# flight_teeny.net
KiCad netlist of a schematic drawn in EAGLE
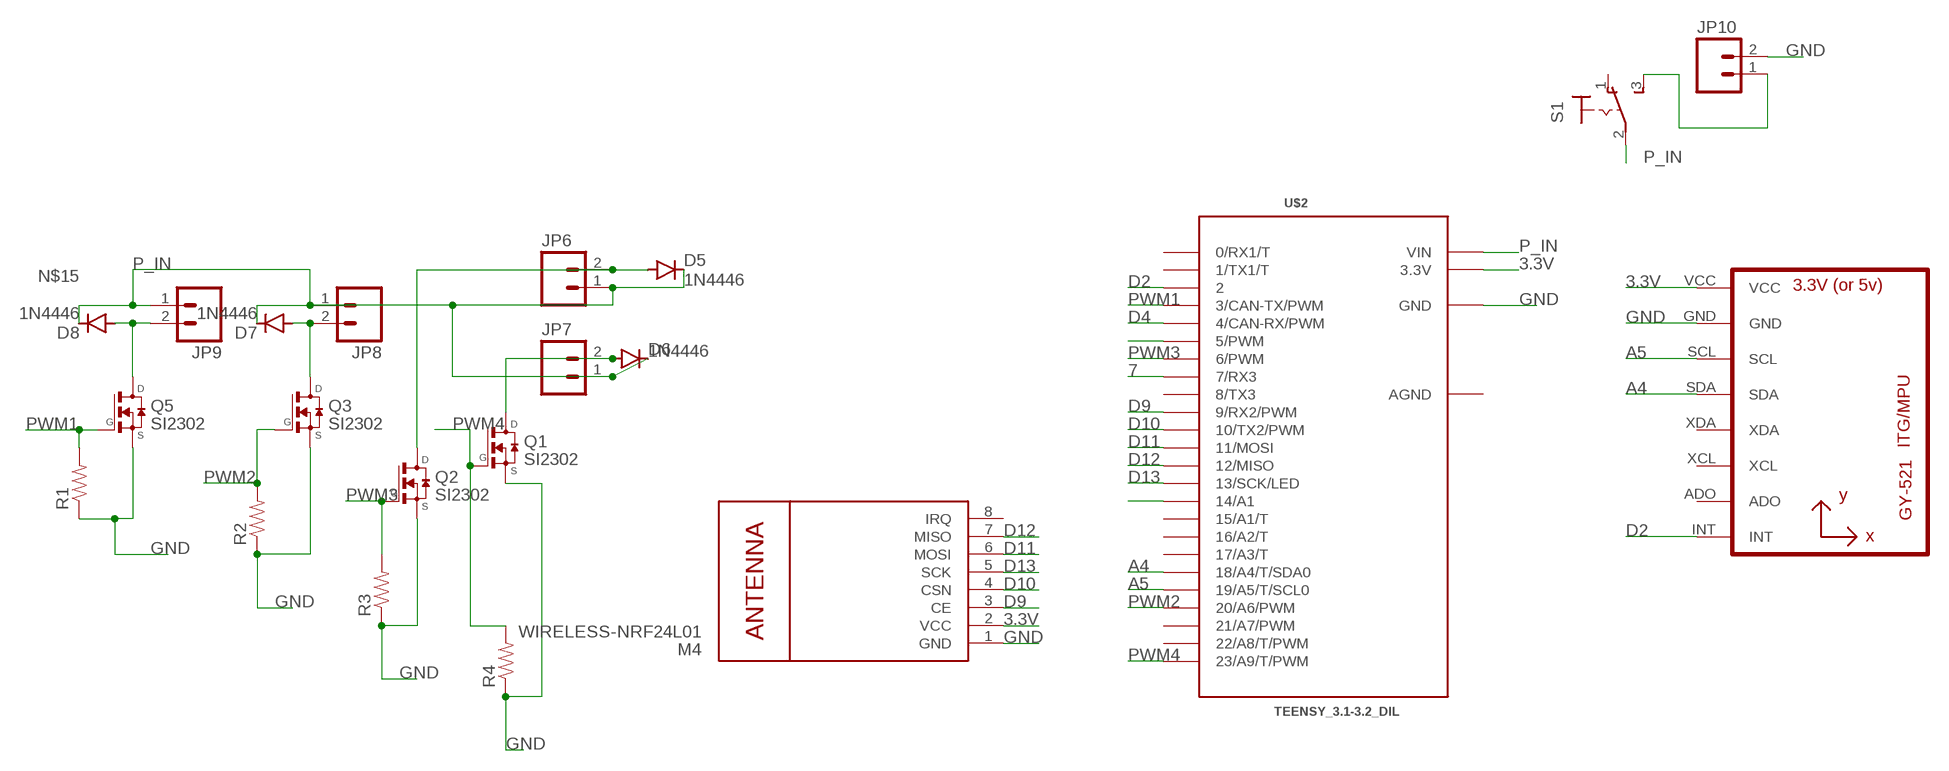
[diagram p0: schematic, sheet 1]

(export (version "E")
  (design (tool "Eeschema 10.0.6"))
  (components
    (comp (ref "D5")
      (value "1N4446")
      (footprint "eagle-import:DO35-10")
      (libsource (lib "eagle-import") (part "1N4446"))
    )
    (comp (ref "D6")
      (value "1N4446")
      (footprint "eagle-import:DO35-10")
      (libsource (lib "eagle-import") (part "1N4446"))
    )
    (comp (ref "D7")
      (value "1N4446")
      (footprint "eagle-import:DO35-10")
      (libsource (lib "eagle-import") (part "1N4446"))
    )
    (comp (ref "D8")
      (value "1N4446")
      (footprint "eagle-import:DO35-10")
      (libsource (lib "eagle-import") (part "1N4446"))
    )
    (comp (ref "JP6")
      (value "M021X02_NO_SILK")
      (footprint "eagle-import:1X02_NO_SILK")
      (libsource (lib "eagle-import") (part "M021X02_NO_SILK"))
    )
    (comp (ref "JP7")
      (value "M021X02_NO_SILK")
      (footprint "eagle-import:1X02_NO_SILK")
      (libsource (lib "eagle-import") (part "M021X02_NO_SILK"))
    )
    (comp (ref "JP8")
      (value "M021X02_NO_SILK")
      (footprint "eagle-import:1X02_NO_SILK")
      (libsource (lib "eagle-import") (part "M021X02_NO_SILK"))
    )
    (comp (ref "JP9")
      (value "M021X02_NO_SILK")
      (footprint "eagle-import:1X02_NO_SILK")
      (libsource (lib "eagle-import") (part "M021X02_NO_SILK"))
    )
    (comp (ref "JP10")
      (value "M02PTH")
      (footprint "eagle-import:1X02")
      (libsource (lib "eagle-import") (part "M02PTH"))
    )
    (comp (ref "M4")
      (value "WIRELESS-NRF24L01")
      (footprint "eagle-import:WIRELESS-NRF24L01")
      (libsource (lib "eagle-import") (part "WIRELESS-NRF24L01"))
    )
    (comp (ref "Q1")
      (value "SI2302")
      (footprint "eagle-import:SOT23")
      (libsource (lib "eagle-import") (part "SI2302"))
    )
    (comp (ref "Q2")
      (value "SI2302")
      (footprint "eagle-import:SOT23")
      (libsource (lib "eagle-import") (part "SI2302"))
    )
    (comp (ref "Q3")
      (value "SI2302")
      (footprint "eagle-import:SOT23")
      (libsource (lib "eagle-import") (part "SI2302"))
    )
    (comp (ref "Q5")
      (value "SI2302")
      (footprint "eagle-import:SOT23")
      (libsource (lib "eagle-import") (part "SI2302"))
    )
    (comp (ref "R1")
      (value "RESISTORAXIAL-0.3")
      (footprint "eagle-import:AXIAL-0.3")
      (libsource (lib "eagle-import") (part "RESISTORAXIAL-0.3"))
    )
    (comp (ref "R2")
      (value "RESISTORAXIAL-0.3")
      (footprint "eagle-import:AXIAL-0.3")
      (libsource (lib "eagle-import") (part "RESISTORAXIAL-0.3"))
    )
    (comp (ref "R3")
      (value "RESISTORAXIAL-0.3")
      (footprint "eagle-import:AXIAL-0.3")
      (libsource (lib "eagle-import") (part "RESISTORAXIAL-0.3"))
    )
    (comp (ref "R4")
      (value "RESISTORAXIAL-0.3")
      (footprint "eagle-import:AXIAL-0.3")
      (libsource (lib "eagle-import") (part "RESISTORAXIAL-0.3"))
    )
    (comp (ref "S1")
      (value "M9040P")
      (footprint "eagle-import:M9040P")
      (libsource (lib "eagle-import") (part "M9040P"))
    )
    (comp (ref "U$2")
      (value "TEENSY_3.1-3.2_DIL")
      (footprint "eagle-import:TEENSY_3.0-3.2&LC_DIL")
      (libsource (lib "eagle-import") (part "TEENSY_3.1-3.2_DIL"))
    )
    (comp (ref "U2")
      (value "GY-521MPU6050")
      (footprint "eagle-import:GY-521")
      (libsource (lib "eagle-import") (part "GY-521MPU6050"))
    )
  )
  (nets
    (net (code "1") (name "/3.3V") (class "Default")
      (node (ref "M4") (pin "2") (pinfunction "VCC_2") (pintype "power_in"))
      (node (ref "U$2") (pin "3.3V") (pinfunction "3.3V_3.3V") (pintype "power_in"))
      (node (ref "U2") (pin "VCC") (pinfunction "VCC_VCC") (pintype "bidirectional"))
    )
    (net (code "2") (name "/7") (class "Default")
      (node (ref "U$2") (pin "7") (pinfunction "7/RX3_7") (pintype "bidirectional"))
    )
    (net (code "3") (name "/A4") (class "Default")
      (node (ref "U$2") (pin "18/A4") (pinfunction "18/A4/T/SDA0_18/A4") (pintype "bidirectional"))
      (node (ref "U2") (pin "SDA") (pinfunction "SDA_SDA") (pintype "bidirectional"))
    )
    (net (code "4") (name "/A5") (class "Default")
      (node (ref "U$2") (pin "19/A5") (pinfunction "19/A5/T/SCL0_19/A5") (pintype "bidirectional"))
      (node (ref "U2") (pin "SCL") (pinfunction "SCL_SCL") (pintype "bidirectional"))
    )
    (net (code "5") (name "/AGND") (class "Default")
      (node (ref "U$2") (pin "AGND") (pinfunction "AGND_AGND") (pintype "power_in"))
    )
    (net (code "6") (name "/D2") (class "Default")
      (node (ref "U$2") (pin "2") (pinfunction "2_2") (pintype "bidirectional"))
      (node (ref "U2") (pin "INT") (pinfunction "INT_INT") (pintype "bidirectional"))
    )
    (net (code "7") (name "/D4") (class "Default")
      (node (ref "U$2") (pin "4") (pinfunction "4/CAN-RX/PWM_4") (pintype "bidirectional"))
    )
    (net (code "8") (name "/D9") (class "Default")
      (node (ref "M4") (pin "3") (pinfunction "CE_3") (pintype "bidirectional"))
      (node (ref "U$2") (pin "9") (pinfunction "9/RX2/PWM_9") (pintype "bidirectional"))
    )
    (net (code "9") (name "/D10") (class "Default")
      (node (ref "M4") (pin "4") (pinfunction "CSN_4") (pintype "bidirectional"))
      (node (ref "U$2") (pin "10") (pinfunction "10/TX2/PWM_10") (pintype "bidirectional"))
    )
    (net (code "10") (name "/D11") (class "Default")
      (node (ref "M4") (pin "6") (pinfunction "MOSI_6") (pintype "bidirectional"))
      (node (ref "U$2") (pin "11") (pinfunction "11/MOSI_11") (pintype "bidirectional"))
    )
    (net (code "11") (name "/D12") (class "Default")
      (node (ref "M4") (pin "7") (pinfunction "MISO_7") (pintype "bidirectional"))
      (node (ref "U$2") (pin "12") (pinfunction "12/MISO_12") (pintype "bidirectional"))
    )
    (net (code "12") (name "/D13") (class "Default")
      (node (ref "M4") (pin "5") (pinfunction "SCK_5") (pintype "bidirectional"))
      (node (ref "U$2") (pin "13") (pinfunction "13/SCK/LED_13") (pintype "bidirectional"))
    )
    (net (code "13") (name "/GND") (class "Default")
      (node (ref "JP10") (pin "2") (pinfunction "2_2") (pintype "passive"))
      (node (ref "M4") (pin "1") (pinfunction "GND_1") (pintype "power_in"))
      (node (ref "Q1") (pin "2") (pinfunction "S_2") (pintype "passive"))
      (node (ref "Q2") (pin "2") (pinfunction "S_2") (pintype "passive"))
      (node (ref "Q3") (pin "2") (pinfunction "S_2") (pintype "passive"))
      (node (ref "Q5") (pin "2") (pinfunction "S_2") (pintype "passive"))
      (node (ref "R1") (pin "P$1") (pinfunction "1_P$1") (pintype "passive"))
      (node (ref "R2") (pin "P$1") (pinfunction "1_P$1") (pintype "passive"))
      (node (ref "R3") (pin "P$1") (pinfunction "1_P$1") (pintype "passive"))
      (node (ref "R4") (pin "P$1") (pinfunction "1_P$1") (pintype "passive"))
      (node (ref "U$2") (pin "GND") (pinfunction "GND_GND") (pintype "power_in"))
      (node (ref "U2") (pin "GND") (pinfunction "GND_GND") (pintype "bidirectional"))
    )
    (net (code "14") (name "/N$15") (class "Default")
      (node (ref "D8") (pin "A") (pinfunction "A_A") (pintype "passive"))
      (node (ref "JP9") (pin "2") (pinfunction "2_2") (pintype "passive"))
      (node (ref "Q5") (pin "3") (pinfunction "D_3") (pintype "passive"))
    )
    (net (code "15") (name "/PWM1") (class "Default")
      (node (ref "Q5") (pin "1") (pinfunction "G_1") (pintype "passive"))
      (node (ref "R1") (pin "P$2") (pinfunction "2_P$2") (pintype "passive"))
      (node (ref "U$2") (pin "3") (pinfunction "3/CAN-TX/PWM_3") (pintype "bidirectional"))
    )
    (net (code "16") (name "/PWM2") (class "Default")
      (node (ref "Q3") (pin "1") (pinfunction "G_1") (pintype "passive"))
      (node (ref "R2") (pin "P$2") (pinfunction "2_P$2") (pintype "passive"))
      (node (ref "U$2") (pin "20/A6") (pinfunction "20/A6/PWM_20/A6") (pintype "bidirectional"))
    )
    (net (code "17") (name "/PWM3") (class "Default")
      (node (ref "Q2") (pin "1") (pinfunction "G_1") (pintype "passive"))
      (node (ref "R3") (pin "P$2") (pinfunction "2_P$2") (pintype "passive"))
      (node (ref "U$2") (pin "6") (pinfunction "6/PWM_6") (pintype "bidirectional"))
    )
    (net (code "18") (name "/PWM4") (class "Default")
      (node (ref "Q1") (pin "1") (pinfunction "G_1") (pintype "passive"))
      (node (ref "R4") (pin "P$2") (pinfunction "2_P$2") (pintype "passive"))
      (node (ref "U$2") (pin "23/A9") (pinfunction "23/A9/T/PWM_23/A9") (pintype "bidirectional"))
    )
    (net (code "19") (name "/P_IN") (class "Default")
      (node (ref "D5") (pin "C") (pinfunction "C_C") (pintype "passive"))
      (node (ref "D6") (pin "C") (pinfunction "C_C") (pintype "passive"))
      (node (ref "D7") (pin "C") (pinfunction "C_C") (pintype "passive"))
      (node (ref "D8") (pin "C") (pinfunction "C_C") (pintype "passive"))
      (node (ref "JP6") (pin "1") (pinfunction "1_1") (pintype "passive"))
      (node (ref "JP7") (pin "1") (pinfunction "1_1") (pintype "passive"))
      (node (ref "JP8") (pin "1") (pinfunction "1_1") (pintype "passive"))
      (node (ref "JP9") (pin "1") (pinfunction "1_1") (pintype "passive"))
      (node (ref "S1") (pin "2") (pinfunction "P_2") (pintype "passive"))
      (node (ref "U$2") (pin "VIN") (pinfunction "VIN_VIN") (pintype "power_in"))
    )
    (net (code "20") (name "Net-(Q1-D)") (class "Default")
      (node (ref "D6") (pin "A") (pinfunction "A_A") (pintype "passive"))
      (node (ref "JP7") (pin "2") (pinfunction "2_2") (pintype "passive"))
      (node (ref "Q1") (pin "3") (pinfunction "D_3") (pintype "passive"))
    )
    (net (code "21") (name "Net-(Q2-D)") (class "Default")
      (node (ref "D5") (pin "A") (pinfunction "A_A") (pintype "passive"))
      (node (ref "JP6") (pin "2") (pinfunction "2_2") (pintype "passive"))
      (node (ref "Q2") (pin "3") (pinfunction "D_3") (pintype "passive"))
    )
    (net (code "22") (name "Net-(Q3-D)") (class "Default")
      (node (ref "D7") (pin "A") (pinfunction "A_A") (pintype "passive"))
      (node (ref "JP8") (pin "2") (pinfunction "2_2") (pintype "passive"))
      (node (ref "Q3") (pin "3") (pinfunction "D_3") (pintype "passive"))
    )
    (net (code "23") (name "Net-(S1-S)") (class "Default")
      (node (ref "JP10") (pin "1") (pinfunction "1_1") (pintype "passive"))
      (node (ref "S1") (pin "3") (pinfunction "S_3") (pintype "passive"))
    )
    (net (code "24") (name "unconnected-(M4-IRQ-Pad8)") (class "Default")
      (node (ref "M4") (pin "8") (pinfunction "IRQ_8") (pintype "bidirectional"))
    )
    (net (code "25") (name "unconnected-(S1-O-Pad1)") (class "Default")
      (node (ref "S1") (pin "1") (pinfunction "O_1") (pintype "passive"))
    )
    (net (code "26") (name "unconnected-(U$2-0{slash}RX1{slash}T-Pad0)") (class "Default")
      (node (ref "U$2") (pin "0") (pinfunction "0/RX1/T_0") (pintype "bidirectional"))
    )
    (net (code "27") (name "unconnected-(U$2-1{slash}TX1{slash}T-Pad1)") (class "Default")
      (node (ref "U$2") (pin "1") (pinfunction "1/TX1/T_1") (pintype "bidirectional"))
    )
    (net (code "28") (name "unconnected-(U$2-5{slash}PWM-Pad5)") (class "Default")
      (node (ref "U$2") (pin "5") (pinfunction "5/PWM_5") (pintype "bidirectional"))
    )
    (net (code "29") (name "unconnected-(U$2-8{slash}TX3-Pad8)") (class "Default")
      (node (ref "U$2") (pin "8") (pinfunction "8/TX3_8") (pintype "bidirectional"))
    )
    (net (code "30") (name "unconnected-(U$2-14{slash}A1-Pad14{slash}A0)") (class "Default")
      (node (ref "U$2") (pin "14/A0") (pinfunction "14/A1_14/A0") (pintype "bidirectional"))
    )
    (net (code "31") (name "unconnected-(U$2-15{slash}A1{slash}T-Pad15{slash}A1)") (class "Default")
      (node (ref "U$2") (pin "15/A1") (pinfunction "15/A1/T_15/A1") (pintype "bidirectional"))
    )
    (net (code "32") (name "unconnected-(U$2-16{slash}A2{slash}T-Pad16{slash}A2)") (class "Default")
      (node (ref "U$2") (pin "16/A2") (pinfunction "16/A2/T_16/A2") (pintype "bidirectional"))
    )
    (net (code "33") (name "unconnected-(U$2-17{slash}A3{slash}T-Pad17{slash}A3)") (class "Default")
      (node (ref "U$2") (pin "17/A3") (pinfunction "17/A3/T_17/A3") (pintype "bidirectional"))
    )
    (net (code "34") (name "unconnected-(U$2-21{slash}A7{slash}PWM-Pad21{slash}A7)") (class "Default")
      (node (ref "U$2") (pin "21/A7") (pinfunction "21/A7/PWM_21/A7") (pintype "bidirectional"))
    )
    (net (code "35") (name "unconnected-(U$2-22{slash}A8{slash}T{slash}PWM-Pad22{slash}A8)") (class "Default")
      (node (ref "U$2") (pin "22/A8") (pinfunction "22/A8/T/PWM_22/A8") (pintype "bidirectional"))
    )
    (net (code "36") (name "unconnected-(U2-PadADO)") (class "Default")
      (node (ref "U2") (pin "ADO") (pinfunction "ADO_ADO") (pintype "bidirectional"))
    )
    (net (code "37") (name "unconnected-(U2-PadXCL)") (class "Default")
      (node (ref "U2") (pin "XCL") (pinfunction "XCL_XCL") (pintype "bidirectional"))
    )
    (net (code "38") (name "unconnected-(U2-PadXDA)") (class "Default")
      (node (ref "U2") (pin "XDA") (pinfunction "XDA_XDA") (pintype "bidirectional"))
    )
  )
)
